# SYSTEM_INTERFACE.net
KiCad netlist of a schematic drawn in Altium Designer
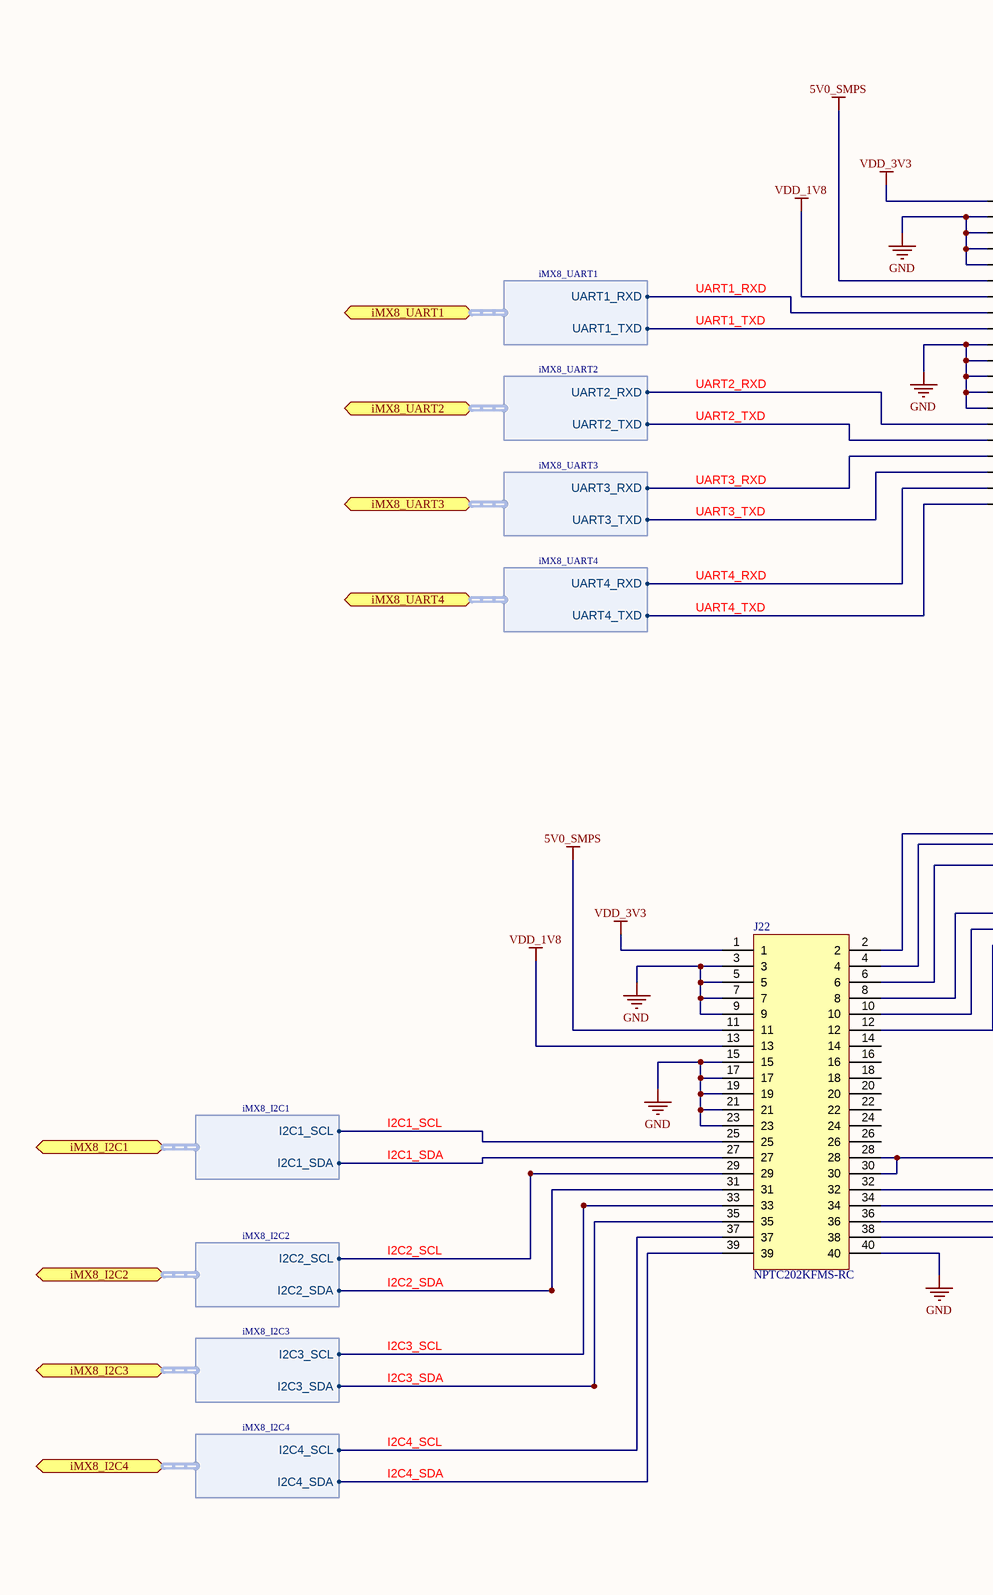
[diagram p0: SYSTEM_INTERFACE.SchDoc, left]
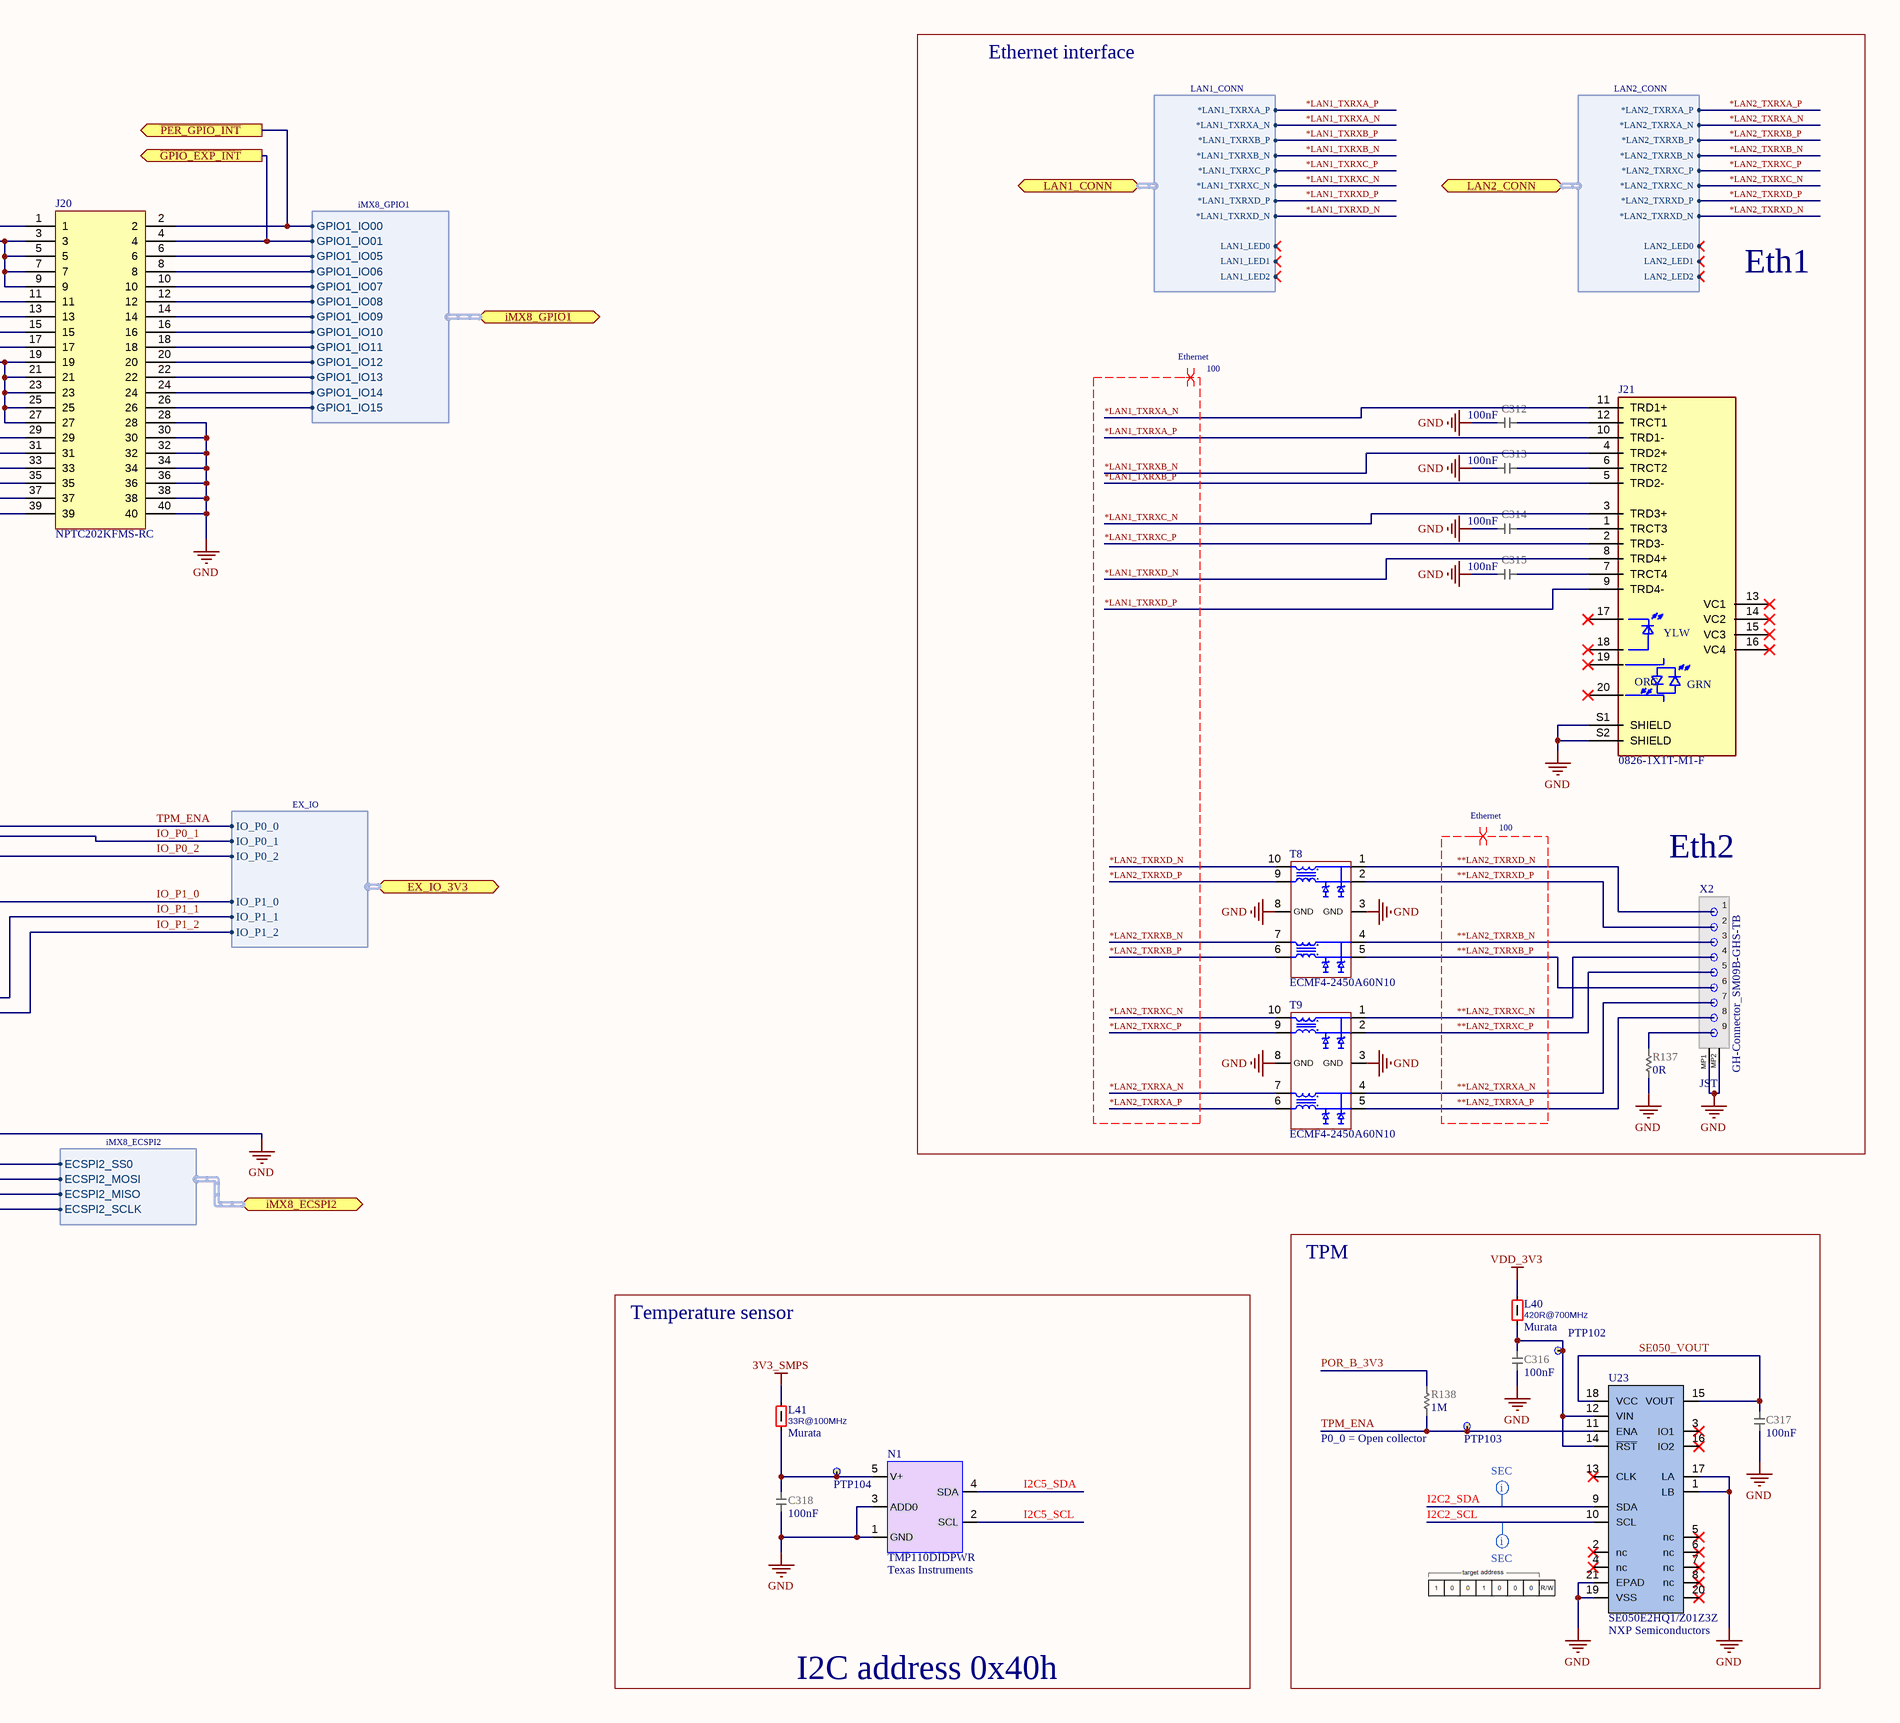
[diagram p1: SYSTEM_INTERFACE.SchDoc, right]

(export (version "E")
  (design (tool "Eeschema 10.0.6"))
  (components
    (comp (ref "C312")
      (value "100nF")
      (footprint "CAP_0201_UN1Q")
      (description "CAP")
      (fields (field (name "PART NUMBER") "GRM033C71C104KE14D") (field (name "MANUFACTURER") "Murata"))
      (libsource (lib "CM5_library") (part "CMP-001-000385-16"))
    )
    (comp (ref "C313")
      (value "100nF")
      (footprint "CAP_0201_UN1Q")
      (description "CAP")
      (fields (field (name "PART NUMBER") "GRM033C71C104KE14D") (field (name "MANUFACTURER") "Murata"))
      (libsource (lib "CM5_library") (part "CMP-001-000385-16"))
    )
    (comp (ref "C314")
      (value "100nF")
      (footprint "CAP_0201_UN1Q")
      (description "CAP")
      (fields (field (name "PART NUMBER") "GRM033C71C104KE14D") (field (name "MANUFACTURER") "Murata"))
      (libsource (lib "CM5_library") (part "CMP-001-000385-16"))
    )
    (comp (ref "C315")
      (value "100nF")
      (footprint "CAP_0201_UN1Q")
      (description "CAP")
      (fields (field (name "PART NUMBER") "GRM033C71C104KE14D") (field (name "MANUFACTURER") "Murata"))
      (libsource (lib "CM5_library") (part "CMP-001-000385-16"))
    )
    (comp (ref "C316")
      (value "100nF")
      (footprint "CAP_0201_UN1Q")
      (description "CAP")
      (fields (field (name "PART NUMBER") "GRM033C71C104KE14D") (field (name "MANUFACTURER") "Murata"))
      (libsource (lib "CM5_library") (part "CMP-001-000385-16"))
    )
    (comp (ref "C317")
      (value "100nF")
      (footprint "CAP_0201_UN1Q")
      (description "CAP")
      (fields (field (name "PART NUMBER") "GRM033C71C104KE14D") (field (name "MANUFACTURER") "Murata"))
      (libsource (lib "CM5_library") (part "CMP-001-000385-16"))
    )
    (comp (ref "C318")
      (value "100nF")
      (footprint "CAP_0201_UN1Q")
      (description "CAP")
      (fields (field (name "PART NUMBER") "GRM033C71C104KE14D") (field (name "MANUFACTURER") "Murata"))
      (libsource (lib "CM5_library") (part "CMP-001-000385-16"))
    )
    (comp (ref "J20")
      (value "NPTC202KFMS-RC")
      (footprint "SULLINS_NPTC202KFMS-RC")
      (fields (field (name "MF") "{'manufacturer': u'Sullins Connector Solutions'}"))
      (libsource (lib "NPTC202KFMS-RC") (part "NPTC202KFMS-RC"))
    )
    (comp (ref "J21")
      (value "0826-1X1T-M1-F")
      (footprint "SnapEDApcb:BEL_0826-1X1T-M1-F")
      (description "MagJack 1000BASE-T ¦ PoE ¦ 1X1 ¦ OG/Y ¦ Tab Up ¦ RoHS")
      (fields (field (name "MF") "Bel Magnetic Solutions"))
      (libsource (lib "SnapEDAsch") (part "0826-1X1T-M1-F"))
    )
    (comp (ref "J22")
      (value "NPTC202KFMS-RC")
      (footprint "SULLINS_NPTC202KFMS-RC")
      (fields (field (name "MF") "{'manufacturer': u'Sullins Connector Solutions'}"))
      (libsource (lib "NPTC202KFMS-RC") (part "NPTC202KFMS-RC"))
    )
    (comp (ref "L40")
      (value "420R@700MHz")
      (footprint "IND_0201_UN1Q")
      (description "FERRITE")
      (fields
        (field (name "MANUFACTURER") "Murata")
        (field (name "TOLERANCE") "25%")
        (field (name "MANUFACTURER_1") "Murata")
      )
      (libsource (lib "CM5_library") (part "CMP-001-000747-7"))
    )
    (comp (ref "L41")
      (value "33R@100MHz")
      (footprint "IND_0201_UN1Q")
      (description "FERRITE")
      (fields
        (field (name "MANUFACTURER") "Murata")
        (field (name "TOLERANCE") "25%")
        (field (name "MANUFACTURER_1") "Murata")
      )
      (libsource (lib "CM5_library") (part "CMP-001-000744-8"))
    )
    (comp (ref "N1")
      (value "TMP110DIDPWR")
      (footprint "X2SON_DPW0005B")
      (description "I2C temperature sensor, X2SON-5")
      (fields
        (field (name "PART NUMBER") "TMP110DIDPWR")
        (field (name "MANUFACTURER") "Texas Instruments")
        (field (name "MANUFACTURER_1") "Texas Instruments")
      )
      (libsource (lib "CM5_library") (part "CMP-001-001548-1"))
    )
    (comp (ref "PTP102")
      (value "PTP_0.4mm")
      (footprint "PTP_0.4mm")
      (description "Production Testpoint 0.4mm. Flying probe. Use 1mm pitch.")
      (fields (field (name "PART NUMBER") "PTP 0.4mm"))
      (libsource (lib "CM5_library") (part "CMP-001-001296-3"))
    )
    (comp (ref "PTP103")
      (value "PTP_0.4mm")
      (footprint "PTP_0.4mm")
      (description "Production Testpoint 0.4mm. Flying probe. Use 1mm pitch.")
      (fields (field (name "PART NUMBER") "PTP 0.4mm"))
      (libsource (lib "CM5_library") (part "CMP-001-001296-3"))
    )
    (comp (ref "PTP104")
      (value "PTP_0.4mm")
      (footprint "PTP_0.4mm")
      (description "Production Testpoint 0.4mm. Flying probe. Use 1mm pitch.")
      (fields (field (name "PART NUMBER") "PTP 0.4mm"))
      (libsource (lib "CM5_library") (part "CMP-001-001296-3"))
    )
    (comp (ref "R137")
      (value "0R")
      (footprint "RES_0201_UN1Q")
      (description "RES")
      (fields (field (name "PART NUMBER") "RC0201JR-070RL") (field (name "MANUFACTURER") "YAGEO"))
      (libsource (lib "CM5_library") (part "CMP-001-000429-13"))
    )
    (comp (ref "R138")
      (value "1M")
      (footprint "RES_0201_UN1Q")
      (description "RES")
      (fields (field (name "MANUFACTURER") "Yageo") (field (name "TOLERANCE") "1%"))
      (libsource (lib "TII_WS") (part "RES_Common"))
    )
    (comp (ref "T8")
      (value "EMI_ESD_ECMF4-2450A60N10")
      (footprint "ECMF4-2450A60N10")
      (description "EMI Filter with ESD, 2x differential pair")
      (fields
        (field (name "MANUFACTURER") "STMicroelectronics")
        (field (name "PART NUMBER") "ECMF4-2450A60N10")
        (field (name "MANUFACTURER PART NUMBER") "ECMF4-2450A60N10")
      )
      (libsource (lib "CM5_library") (part "CMP-001-001620-1"))
    )
    (comp (ref "T9")
      (value "EMI_ESD_ECMF4-2450A60N10")
      (footprint "ECMF4-2450A60N10")
      (description "EMI Filter with ESD, 2x differential pair")
      (fields
        (field (name "MANUFACTURER") "STMicroelectronics")
        (field (name "PART NUMBER") "ECMF4-2450A60N10")
        (field (name "MANUFACTURER PART NUMBER") "ECMF4-2450A60N10")
      )
      (libsource (lib "CM5_library") (part "CMP-001-001620-1"))
    )
    (comp (ref "U23")
      (value "SE050E2HQ1/Z01Z3Z")
      (footprint "HX2QFN20_NXP")
      (description "TPM")
      (fields
        (field (name "MANUFACTURER") "NXP USA Inc.")
        (field (name "PART NUMBER") "SE050E2HQ1/Z01Z3Z")
        (field (name "MANUFACTURER_1") "NXP Semiconductors")
      )
      (libsource (lib "CM5_library") (part "CMP-001-001414-1"))
    )
    (comp (ref "X2")
      (value "GH-Connector_SM09B-GHS-TB")
      (footprint "SM09B-GHS-TB")
      (description "JST GH Connector, Header, 9 pin, Horizontal, Pitch 1.25 mm")
      (fields
        (field (name "MANUFACTURER") "JST")
        (field (name "PART NUMBER") "SM09B-GHS-TB")
        (field (name "MANUFACTURER_1") "JST")
      )
      (libsource (lib "CM5_library") (part "CMP-001-000097-10"))
    )
  )
  (nets
    (net (code "14") (name "/**LAN2_TXRXA_N") (class "Default")
      (node (ref "T9") (pin "4") (pinfunction "D2+_4") (pintype "passive"))
      (node (ref "X2") (pin "7") (pinfunction "7_7") (pintype "passive"))
    )
    (net (code "15") (name "/**LAN2_TXRXA_P") (class "Default")
      (node (ref "T9") (pin "5") (pinfunction "D2-_5") (pintype "passive"))
      (node (ref "X2") (pin "8") (pinfunction "8_8") (pintype "passive"))
    )
    (net (code "16") (name "/**LAN2_TXRXB_N") (class "Default")
      (node (ref "T8") (pin "4") (pinfunction "D2+_4") (pintype "passive"))
      (node (ref "X2") (pin "3") (pinfunction "3_3") (pintype "passive"))
    )
    (net (code "17") (name "/**LAN2_TXRXB_P") (class "Default")
      (node (ref "T8") (pin "5") (pinfunction "D2-_5") (pintype "passive"))
      (node (ref "X2") (pin "6") (pinfunction "6_6") (pintype "passive"))
    )
    (net (code "18") (name "/**LAN2_TXRXC_N") (class "Default")
      (node (ref "T9") (pin "1") (pinfunction "D1+_1") (pintype "passive"))
      (node (ref "X2") (pin "4") (pinfunction "4_4") (pintype "passive"))
    )
    (net (code "19") (name "/**LAN2_TXRXC_P") (class "Default")
      (node (ref "T9") (pin "2") (pinfunction "D1-_2") (pintype "passive"))
      (node (ref "X2") (pin "5") (pinfunction "5_5") (pintype "passive"))
    )
    (net (code "20") (name "/**LAN2_TXRXD_N") (class "Default")
      (node (ref "T8") (pin "1") (pinfunction "D1+_1") (pintype "passive"))
      (node (ref "X2") (pin "1") (pinfunction "1_1") (pintype "passive"))
    )
    (net (code "21") (name "/**LAN2_TXRXD_P") (class "Default")
      (node (ref "T8") (pin "2") (pinfunction "D1-_2") (pintype "passive"))
      (node (ref "X2") (pin "2") (pinfunction "2_2") (pintype "passive"))
    )
    (net (code "22") (name "/*LAN1_TXRXA_N") (class "Default")
      (node (ref "J21") (pin "11") (pinfunction "TRD1+_11") (pintype "passive"))
    )
    (net (code "23") (name "/*LAN1_TXRXA_P") (class "Default")
      (node (ref "J21") (pin "10") (pinfunction "TRD1-_10") (pintype "passive"))
    )
    (net (code "24") (name "/*LAN1_TXRXB_N") (class "Default")
      (node (ref "J21") (pin "4") (pinfunction "TRD2+_4") (pintype "passive"))
    )
    (net (code "25") (name "/*LAN1_TXRXB_P") (class "Default")
      (node (ref "J21") (pin "5") (pinfunction "TRD2-_5") (pintype "passive"))
    )
    (net (code "26") (name "/*LAN1_TXRXC_N") (class "Default")
      (node (ref "J21") (pin "3") (pinfunction "TRD3+_3") (pintype "passive"))
    )
    (net (code "27") (name "/*LAN1_TXRXC_P") (class "Default")
      (node (ref "J21") (pin "2") (pinfunction "TRD3-_2") (pintype "passive"))
    )
    (net (code "28") (name "/*LAN1_TXRXD_N") (class "Default")
      (node (ref "J21") (pin "8") (pinfunction "TRD4+_8") (pintype "passive"))
    )
    (net (code "29") (name "/*LAN1_TXRXD_P") (class "Default")
      (node (ref "J21") (pin "9") (pinfunction "TRD4-_9") (pintype "passive"))
    )
    (net (code "30") (name "/*LAN2_TXRXA_N") (class "Default")
      (node (ref "T9") (pin "7") (pinfunction "D2+_IC_7") (pintype "passive"))
    )
    (net (code "31") (name "/*LAN2_TXRXA_P") (class "Default")
      (node (ref "T9") (pin "6") (pinfunction "D2-_IC_6") (pintype "passive"))
    )
    (net (code "32") (name "/*LAN2_TXRXB_N") (class "Default")
      (node (ref "T8") (pin "7") (pinfunction "D2+_IC_7") (pintype "passive"))
    )
    (net (code "33") (name "/*LAN2_TXRXB_P") (class "Default")
      (node (ref "T8") (pin "6") (pinfunction "D2-_IC_6") (pintype "passive"))
    )
    (net (code "34") (name "/*LAN2_TXRXC_N") (class "Default")
      (node (ref "T9") (pin "10") (pinfunction "D1+_IC_10") (pintype "passive"))
    )
    (net (code "35") (name "/*LAN2_TXRXC_P") (class "Default")
      (node (ref "T9") (pin "9") (pinfunction "D1-_IC_9") (pintype "passive"))
    )
    (net (code "36") (name "/*LAN2_TXRXD_N") (class "Default")
      (node (ref "T8") (pin "10") (pinfunction "D1+_IC_10") (pintype "passive"))
    )
    (net (code "37") (name "/*LAN2_TXRXD_P") (class "Default")
      (node (ref "T8") (pin "9") (pinfunction "D1-_IC_9") (pintype "passive"))
    )
    (net (code "38") (name "/ECSPI2_MISO") (class "Default")
      (node (ref "J22") (pin "36") (pinfunction "36_36") (pintype "passive"))
    )
    (net (code "39") (name "/ECSPI2_MOSI") (class "Default")
      (node (ref "J22") (pin "34") (pinfunction "34_34") (pintype "passive"))
    )
    (net (code "40") (name "/ECSPI2_SCLK") (class "Default")
      (node (ref "J22") (pin "38") (pinfunction "38_38") (pintype "passive"))
    )
    (net (code "41") (name "/ECSPI2_SS0") (class "Default")
      (node (ref "J22") (pin "32") (pinfunction "32_32") (pintype "passive"))
    )
    (net (code "42") (name "/GPIO1_IO05") (class "Default")
      (node (ref "J20") (pin "6") (pinfunction "6_6") (pintype "passive"))
    )
    (net (code "43") (name "/GPIO1_IO06") (class "Default")
      (node (ref "J20") (pin "8") (pinfunction "8_8") (pintype "passive"))
    )
    (net (code "44") (name "/GPIO1_IO07") (class "Default")
      (node (ref "J20") (pin "10") (pinfunction "10_10") (pintype "passive"))
    )
    (net (code "45") (name "/GPIO1_IO08") (class "Default")
      (node (ref "J20") (pin "12") (pinfunction "12_12") (pintype "passive"))
    )
    (net (code "46") (name "/GPIO1_IO09") (class "Default")
      (node (ref "J20") (pin "14") (pinfunction "14_14") (pintype "passive"))
    )
    (net (code "47") (name "/GPIO1_IO10") (class "Default")
      (node (ref "J20") (pin "16") (pinfunction "16_16") (pintype "passive"))
    )
    (net (code "48") (name "/GPIO1_IO11") (class "Default")
      (node (ref "J20") (pin "18") (pinfunction "18_18") (pintype "passive"))
    )
    (net (code "49") (name "/GPIO1_IO12") (class "Default")
      (node (ref "J20") (pin "20") (pinfunction "20_20") (pintype "passive"))
    )
    (net (code "50") (name "/GPIO1_IO13") (class "Default")
      (node (ref "J20") (pin "22") (pinfunction "22_22") (pintype "passive"))
    )
    (net (code "51") (name "/GPIO1_IO14") (class "Default")
      (node (ref "J20") (pin "24") (pinfunction "24_24") (pintype "passive"))
    )
    (net (code "52") (name "/GPIO1_IO15") (class "Default")
      (node (ref "J20") (pin "26") (pinfunction "26_26") (pintype "passive"))
    )
    (net (code "53") (name "/GPIO_EXP_INT") (class "Default")
      (node (ref "J20") (pin "4") (pinfunction "4_4") (pintype "passive"))
    )
    (net (code "54") (name "/I2C1_SCL") (class "Default")
      (node (ref "J22") (pin "25") (pinfunction "25_25") (pintype "passive"))
    )
    (net (code "55") (name "/I2C1_SDA") (class "Default")
      (node (ref "J22") (pin "27") (pinfunction "27_27") (pintype "passive"))
    )
    (net (code "56") (name "/I2C2_SCL") (class "Default")
      (node (ref "J22") (pin "29") (pinfunction "29_29") (pintype "passive"))
      (node (ref "U23") (pin "10") (pinfunction "SCL_10") (pintype "passive"))
    )
    (net (code "57") (name "/I2C2_SDA") (class "Default")
      (node (ref "J22") (pin "31") (pinfunction "31_31") (pintype "passive"))
      (node (ref "U23") (pin "9") (pinfunction "SDA_9") (pintype "passive"))
    )
    (net (code "58") (name "/I2C3_SCL") (class "Default")
      (node (ref "J22") (pin "33") (pinfunction "33_33") (pintype "passive"))
    )
    (net (code "59") (name "/I2C3_SDA") (class "Default")
      (node (ref "J22") (pin "35") (pinfunction "35_35") (pintype "passive"))
    )
    (net (code "60") (name "/I2C4_SCL") (class "Default")
      (node (ref "J22") (pin "37") (pinfunction "37_37") (pintype "passive"))
    )
    (net (code "61") (name "/I2C4_SDA") (class "Default")
      (node (ref "J22") (pin "39") (pinfunction "39_39") (pintype "passive"))
    )
    (net (code "62") (name "/I2C5_SCL") (class "Default")
      (node (ref "N1") (pin "2") (pinfunction "SCL_2") (pintype "passive"))
    )
    (net (code "63") (name "/I2C5_SDA") (class "Default")
      (node (ref "N1") (pin "4") (pinfunction "SDA_4") (pintype "passive"))
    )
    (net (code "64") (name "/IO_P0_1") (class "Default")
      (node (ref "J22") (pin "4") (pinfunction "4_4") (pintype "passive"))
    )
    (net (code "65") (name "/IO_P0_2") (class "Default")
      (node (ref "J22") (pin "6") (pinfunction "6_6") (pintype "passive"))
    )
    (net (code "66") (name "/IO_P1_0") (class "Default")
      (node (ref "J22") (pin "8") (pinfunction "8_8") (pintype "passive"))
    )
    (net (code "67") (name "/IO_P1_1") (class "Default")
      (node (ref "J22") (pin "10") (pinfunction "10_10") (pintype "passive"))
    )
    (net (code "68") (name "/IO_P1_2") (class "Default")
      (node (ref "J22") (pin "12") (pinfunction "12_12") (pintype "passive"))
    )
    (net (code "69") (name "/PER_GPIO_INT") (class "Default")
      (node (ref "J20") (pin "2") (pinfunction "2_2") (pintype "passive"))
    )
    (net (code "70") (name "/POR_B_3V3") (class "Default")
      (node (ref "R138") (pin "2") (pinfunction "2_2") (pintype "passive"))
    )
    (net (code "71") (name "/SE050_VOUT") (class "Default")
      (node (ref "C317") (pin "2") (pinfunction "2_2") (pintype "passive"))
      (node (ref "U23") (pin "15") (pinfunction "VOUT_15") (pintype "power_in"))
      (node (ref "U23") (pin "18") (pinfunction "VCC_18") (pintype "power_in"))
    )
    (net (code "72") (name "/TPM_ENA") (class "Default")
      (node (ref "J22") (pin "2") (pinfunction "2_2") (pintype "passive"))
      (node (ref "PTP103") (pin "1") (pinfunction "TP_1") (pintype "passive"))
      (node (ref "R138") (pin "1") (pinfunction "1_1") (pintype "passive"))
      (node (ref "U23") (pin "11") (pinfunction "ENA_11") (pintype "passive"))
    )
    (net (code "73") (name "/UART1_RXD") (class "Default")
      (node (ref "J20") (pin "15") (pinfunction "15_15") (pintype "passive"))
    )
    (net (code "74") (name "/UART1_TXD") (class "Default")
      (node (ref "J20") (pin "17") (pinfunction "17_17") (pintype "passive"))
    )
    (net (code "75") (name "/UART2_RXD") (class "Default")
      (node (ref "J20") (pin "29") (pinfunction "29_29") (pintype "passive"))
    )
    (net (code "76") (name "/UART2_TXD") (class "Default")
      (node (ref "J20") (pin "31") (pinfunction "31_31") (pintype "passive"))
    )
    (net (code "77") (name "/UART3_RXD") (class "Default")
      (node (ref "J20") (pin "33") (pinfunction "33_33") (pintype "passive"))
    )
    (net (code "78") (name "/UART3_TXD") (class "Default")
      (node (ref "J20") (pin "35") (pinfunction "35_35") (pintype "passive"))
    )
    (net (code "79") (name "/UART4_RXD") (class "Default")
      (node (ref "J20") (pin "37") (pinfunction "37_37") (pintype "passive"))
    )
    (net (code "80") (name "/UART4_TXD") (class "Default")
      (node (ref "J20") (pin "39") (pinfunction "39_39") (pintype "passive"))
    )
    (net (code "94") (name "3V3_SMPS") (class "Default")
      (node (ref "L41") (pin "2") (pinfunction "2_2") (pintype "passive"))
    )
    (net (code "95") (name "5V0_SMPS") (class "Default")
      (node (ref "J20") (pin "11") (pinfunction "11_11") (pintype "passive"))
      (node (ref "J22") (pin "11") (pinfunction "11_11") (pintype "passive"))
    )
    (net (code "96") (name "GND") (class "Default")
      (node (ref "C312") (pin "1") (pinfunction "1_1") (pintype "passive"))
      (node (ref "C313") (pin "1") (pinfunction "1_1") (pintype "passive"))
      (node (ref "C314") (pin "1") (pinfunction "1_1") (pintype "passive"))
      (node (ref "C315") (pin "1") (pinfunction "1_1") (pintype "passive"))
      (node (ref "C316") (pin "2") (pinfunction "2_2") (pintype "passive"))
      (node (ref "C317") (pin "1") (pinfunction "1_1") (pintype "passive"))
      (node (ref "C318") (pin "2") (pinfunction "2_2") (pintype "passive"))
      (node (ref "J20") (pin "19") (pinfunction "19_19") (pintype "passive"))
      (node (ref "J20") (pin "21") (pinfunction "21_21") (pintype "passive"))
      (node (ref "J20") (pin "23") (pinfunction "23_23") (pintype "passive"))
      (node (ref "J20") (pin "25") (pinfunction "25_25") (pintype "passive"))
      (node (ref "J20") (pin "27") (pinfunction "27_27") (pintype "passive"))
      (node (ref "J20") (pin "28") (pinfunction "28_28") (pintype "passive"))
      (node (ref "J20") (pin "3") (pinfunction "3_3") (pintype "passive"))
      (node (ref "J20") (pin "30") (pinfunction "30_30") (pintype "passive"))
      (node (ref "J20") (pin "32") (pinfunction "32_32") (pintype "passive"))
      (node (ref "J20") (pin "34") (pinfunction "34_34") (pintype "passive"))
      (node (ref "J20") (pin "36") (pinfunction "36_36") (pintype "passive"))
      (node (ref "J20") (pin "38") (pinfunction "38_38") (pintype "passive"))
      (node (ref "J20") (pin "40") (pinfunction "40_40") (pintype "passive"))
      (node (ref "J20") (pin "5") (pinfunction "5_5") (pintype "passive"))
      (node (ref "J20") (pin "7") (pinfunction "7_7") (pintype "passive"))
      (node (ref "J20") (pin "9") (pinfunction "9_9") (pintype "passive"))
      (node (ref "J21") (pin "S1") (pinfunction "SHIELD_S1") (pintype "passive"))
      (node (ref "J21") (pin "S2") (pinfunction "SHIELD_S2") (pintype "passive"))
      (node (ref "J22") (pin "15") (pinfunction "15_15") (pintype "passive"))
      (node (ref "J22") (pin "17") (pinfunction "17_17") (pintype "passive"))
      (node (ref "J22") (pin "19") (pinfunction "19_19") (pintype "passive"))
      (node (ref "J22") (pin "21") (pinfunction "21_21") (pintype "passive"))
      (node (ref "J22") (pin "23") (pinfunction "23_23") (pintype "passive"))
      (node (ref "J22") (pin "28") (pinfunction "28_28") (pintype "passive"))
      (node (ref "J22") (pin "3") (pinfunction "3_3") (pintype "passive"))
      (node (ref "J22") (pin "30") (pinfunction "30_30") (pintype "passive"))
      (node (ref "J22") (pin "40") (pinfunction "40_40") (pintype "passive"))
      (node (ref "J22") (pin "5") (pinfunction "5_5") (pintype "passive"))
      (node (ref "J22") (pin "7") (pinfunction "7_7") (pintype "passive"))
      (node (ref "J22") (pin "9") (pinfunction "9_9") (pintype "passive"))
      (node (ref "N1") (pin "1") (pinfunction "GND_1") (pintype "power_in"))
      (node (ref "N1") (pin "3") (pinfunction "ADD0_3") (pintype "passive"))
      (node (ref "R137") (pin "2") (pinfunction "2_2") (pintype "passive"))
      (node (ref "T8") (pin "3") (pinfunction "GND_3") (pintype "passive"))
      (node (ref "T8") (pin "8") (pinfunction "GND_8") (pintype "passive"))
      (node (ref "T9") (pin "3") (pinfunction "GND_3") (pintype "passive"))
      (node (ref "T9") (pin "8") (pinfunction "GND_8") (pintype "passive"))
      (node (ref "U23") (pin "1") (pinfunction "LB_1") (pintype "passive"))
      (node (ref "U23") (pin "17") (pinfunction "LA_17") (pintype "power_in"))
      (node (ref "U23") (pin "19") (pinfunction "VSS_19") (pintype "power_in"))
      (node (ref "U23") (pin "21") (pinfunction "EPAD_21") (pintype "power_in"))
      (node (ref "X2") (pin "MP1") (pinfunction "MP1_MP1") (pintype "passive"))
      (node (ref "X2") (pin "MP2") (pinfunction "MP2_MP2") (pintype "passive"))
    )
    (net (code "97") (name "Net-(J21-TRCT1)") (class "Default")
      (node (ref "C312") (pin "2") (pinfunction "2_2") (pintype "passive"))
      (node (ref "J21") (pin "12") (pinfunction "TRCT1_12") (pintype "passive"))
    )
    (net (code "98") (name "Net-(J21-TRCT2)") (class "Default")
      (node (ref "C313") (pin "2") (pinfunction "2_2") (pintype "passive"))
      (node (ref "J21") (pin "6") (pinfunction "TRCT2_6") (pintype "passive"))
    )
    (net (code "99") (name "Net-(J21-TRCT3)") (class "Default")
      (node (ref "C314") (pin "2") (pinfunction "2_2") (pintype "passive"))
      (node (ref "J21") (pin "1") (pinfunction "TRCT3_1") (pintype "passive"))
    )
    (net (code "100") (name "Net-(J21-TRCT4)") (class "Default")
      (node (ref "C315") (pin "2") (pinfunction "2_2") (pintype "passive"))
      (node (ref "J21") (pin "7") (pinfunction "TRCT4_7") (pintype "passive"))
    )
    (net (code "101") (name "Net-(N1-V+)") (class "Default")
      (node (ref "C318") (pin "1") (pinfunction "1_1") (pintype "passive"))
      (node (ref "L41") (pin "1") (pinfunction "1_1") (pintype "passive"))
      (node (ref "N1") (pin "5") (pinfunction "V+_5") (pintype "power_in"))
      (node (ref "PTP104") (pin "1") (pinfunction "TP_1") (pintype "passive"))
    )
    (net (code "102") (name "Net-(PTP102-TP)") (class "Default")
      (node (ref "C316") (pin "1") (pinfunction "1_1") (pintype "passive"))
      (node (ref "L40") (pin "1") (pinfunction "1_1") (pintype "passive"))
      (node (ref "PTP102") (pin "1") (pinfunction "TP_1") (pintype "passive"))
      (node (ref "U23") (pin "12") (pinfunction "VIN_12") (pintype "passive"))
      (node (ref "U23") (pin "14") (pinfunction "RST_14") (pintype "power_in"))
    )
    (net (code "103") (name "Net-(R137-Pad1)") (class "Default")
      (node (ref "R137") (pin "1") (pinfunction "1_1") (pintype "passive"))
      (node (ref "X2") (pin "9") (pinfunction "9_9") (pintype "passive"))
    )
    (net (code "104") (name "VDD_1V8") (class "Default")
      (node (ref "J20") (pin "13") (pinfunction "13_13") (pintype "passive"))
      (node (ref "J22") (pin "13") (pinfunction "13_13") (pintype "passive"))
    )
    (net (code "105") (name "VDD_3V3") (class "Default")
      (node (ref "J20") (pin "1") (pinfunction "1_1") (pintype "passive"))
      (node (ref "J22") (pin "1") (pinfunction "1_1") (pintype "passive"))
      (node (ref "L40") (pin "2") (pinfunction "2_2") (pintype "passive"))
    )
    (net (code "106") (name "unconnected-(J21-Pad17)") (class "Default")
      (node (ref "J21") (pin "17") (pinfunction "17_17") (pintype "passive+no_connect"))
    )
    (net (code "107") (name "unconnected-(J21-Pad18)") (class "Default")
      (node (ref "J21") (pin "18") (pinfunction "18_18") (pintype "passive+no_connect"))
    )
    (net (code "108") (name "unconnected-(J21-Pad19)") (class "Default")
      (node (ref "J21") (pin "19") (pinfunction "19_19") (pintype "passive+no_connect"))
    )
    (net (code "109") (name "unconnected-(J21-Pad20)") (class "Default")
      (node (ref "J21") (pin "20") (pinfunction "20_20") (pintype "passive+no_connect"))
    )
    (net (code "110") (name "unconnected-(J21-VC1-Pad13)") (class "Default")
      (node (ref "J21") (pin "13") (pinfunction "VC1_13") (pintype "passive+no_connect"))
    )
    (net (code "111") (name "unconnected-(J21-VC2-Pad14)") (class "Default")
      (node (ref "J21") (pin "14") (pinfunction "VC2_14") (pintype "passive+no_connect"))
    )
    (net (code "112") (name "unconnected-(J21-VC3-Pad15)") (class "Default")
      (node (ref "J21") (pin "15") (pinfunction "VC3_15") (pintype "passive+no_connect"))
    )
    (net (code "113") (name "unconnected-(J21-VC4-Pad16)") (class "Default")
      (node (ref "J21") (pin "16") (pinfunction "VC4_16") (pintype "passive+no_connect"))
    )
    (net (code "114") (name "unconnected-(J22-Pad14)") (class "Default")
      (node (ref "J22") (pin "14") (pinfunction "14_14") (pintype "passive"))
    )
    (net (code "115") (name "unconnected-(J22-Pad16)") (class "Default")
      (node (ref "J22") (pin "16") (pinfunction "16_16") (pintype "passive"))
    )
    (net (code "116") (name "unconnected-(J22-Pad18)") (class "Default")
      (node (ref "J22") (pin "18") (pinfunction "18_18") (pintype "passive"))
    )
    (net (code "117") (name "unconnected-(J22-Pad20)") (class "Default")
      (node (ref "J22") (pin "20") (pinfunction "20_20") (pintype "passive"))
    )
    (net (code "118") (name "unconnected-(J22-Pad22)") (class "Default")
      (node (ref "J22") (pin "22") (pinfunction "22_22") (pintype "passive"))
    )
    (net (code "119") (name "unconnected-(J22-Pad24)") (class "Default")
      (node (ref "J22") (pin "24") (pinfunction "24_24") (pintype "passive"))
    )
    (net (code "120") (name "unconnected-(J22-Pad26)") (class "Default")
      (node (ref "J22") (pin "26") (pinfunction "26_26") (pintype "passive"))
    )
    (net (code "121") (name "unconnected-(U23-CLK-Pad13)") (class "Default")
      (node (ref "U23") (pin "13") (pinfunction "CLK_13") (pintype "passive+no_connect"))
    )
    (net (code "122") (name "unconnected-(U23-IO1-Pad3)") (class "Default")
      (node (ref "U23") (pin "3") (pinfunction "IO1_3") (pintype "passive+no_connect"))
    )
    (net (code "123") (name "unconnected-(U23-IO2-Pad16)") (class "Default")
      (node (ref "U23") (pin "16") (pinfunction "IO2_16") (pintype "passive+no_connect"))
    )
    (net (code "124") (name "unconnected-(U23-nc-Pad2)") (class "Default")
      (node (ref "U23") (pin "2") (pinfunction "nc_2") (pintype "passive+no_connect"))
    )
    (net (code "125") (name "unconnected-(U23-nc-Pad4)") (class "Default")
      (node (ref "U23") (pin "4") (pinfunction "nc_4") (pintype "passive+no_connect"))
    )
    (net (code "126") (name "unconnected-(U23-nc-Pad5)") (class "Default")
      (node (ref "U23") (pin "5") (pinfunction "nc_5") (pintype "passive+no_connect"))
    )
    (net (code "127") (name "unconnected-(U23-nc-Pad6)") (class "Default")
      (node (ref "U23") (pin "6") (pinfunction "nc_6") (pintype "power_in+no_connect"))
    )
    (net (code "128") (name "unconnected-(U23-nc-Pad7)") (class "Default")
      (node (ref "U23") (pin "7") (pinfunction "nc_7") (pintype "passive+no_connect"))
    )
    (net (code "129") (name "unconnected-(U23-nc-Pad8)") (class "Default")
      (node (ref "U23") (pin "8") (pinfunction "nc_8") (pintype "passive+no_connect"))
    )
    (net (code "130") (name "unconnected-(U23-nc-Pad20)") (class "Default")
      (node (ref "U23") (pin "20") (pinfunction "nc_20") (pintype "power_in+no_connect"))
    )
  )
)
